# INERTIAL.net
KiCad netlist of a schematic drawn in Altium Designer
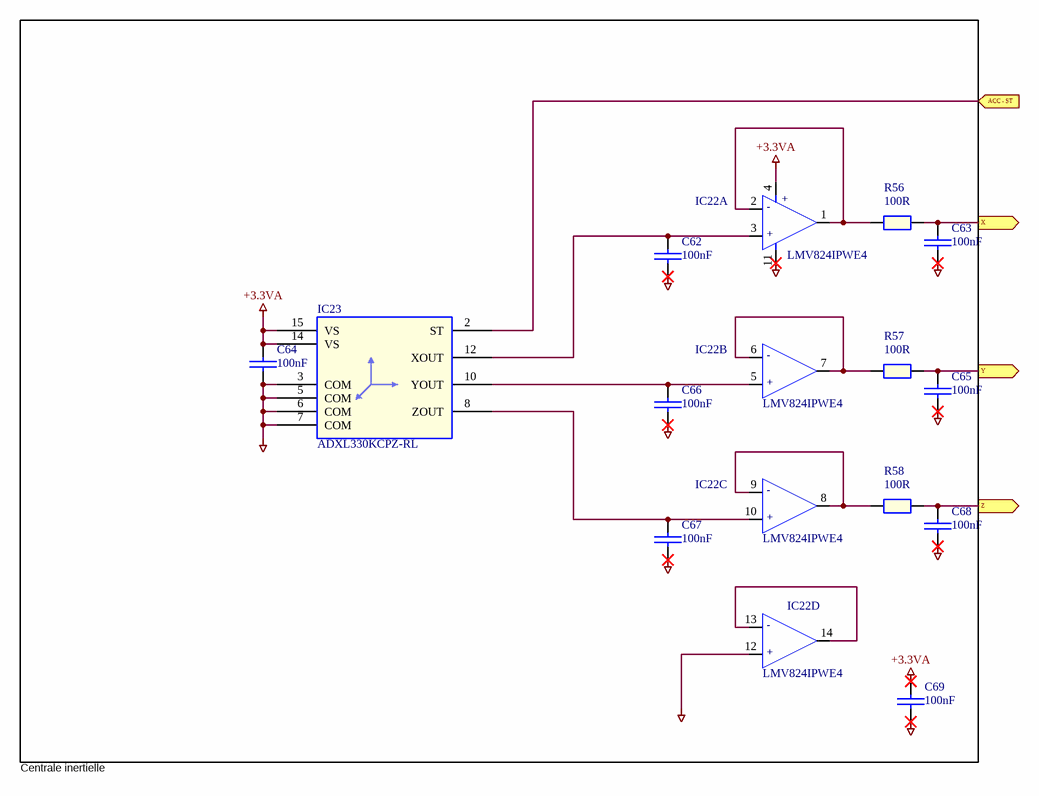
[diagram p0: INERTIAL.SchDoc]

(export (version "E")
  (design (tool "Eeschema 10.0.6"))
  (components
    (comp (ref "C62") (value "100nF") (footprint "SM/C_0805") (libsource (lib "*") (part "C_Dup1")))
    (comp (ref "C63") (value "100nF") (footprint "SM/C_0805") (libsource (lib "*") (part "C_Dup1")))
    (comp (ref "C64") (value "100nF") (footprint "SM/C_0805") (libsource (lib "*") (part "C_Dup1")))
    (comp (ref "C65") (value "100nF") (footprint "SM/C_0805") (libsource (lib "*") (part "C_Dup1")))
    (comp (ref "C66") (value "100nF") (footprint "SM/C_0805") (libsource (lib "*") (part "C_Dup1")))
    (comp (ref "C67") (value "100nF") (footprint "SM/C_0805") (libsource (lib "*") (part "C_Dup1")))
    (comp (ref "C68") (value "100nF") (footprint "SM/C_0805") (libsource (lib "*") (part "C_Dup1")))
    (comp (ref "C69") (value "100nF") (footprint "SM/C_0805") (libsource (lib "*") (part "C_Dup1")))
    (comp (ref "IC22")
      (value "LMV824IPWE4")
      (footprint "HEIG/SM/TSSOP14")
      (libsource (lib "*") (part "AD8609_0"))
    )
    (comp (ref "IC23")
      (value "ADXL330KCPZ-RL")
      (footprint "HEIG/IC/ADXL330")
      (libsource (lib "*") (part "ADXL330"))
    )
    (comp (ref "R56") (value "100R") (footprint "R400") (libsource (lib "*") (part "R_Dup1")))
    (comp (ref "R57") (value "100R") (footprint "R400") (libsource (lib "*") (part "R_Dup1")))
    (comp (ref "R58") (value "100R") (footprint "R400") (libsource (lib "*") (part "R_Dup1")))
  )
  (nets
    (net (code "1") (name "+3.3VA") (class "Default")
      (node (ref "C64") (pin "1") (pinfunction "1_1") (pintype "passive"))
      (node (ref "C69") (pin "1") (pinfunction "1_1") (pintype "passive"))
      (node (ref "IC22") (pin "4") (pinfunction "V+_4") (pintype "passive"))
      (node (ref "IC23") (pin "14") (pinfunction "VS_14") (pintype "passive"))
      (node (ref "IC23") (pin "15") (pinfunction "VS_15") (pintype "passive"))
    )
    (net (code "2") (name "/ACC - ST") (class "Default")
      (node (ref "IC23") (pin "2") (pinfunction "ST_2") (pintype "passive"))
    )
    (net (code "3") (name "/X") (class "Default")
      (node (ref "C63") (pin "1") (pinfunction "1_1") (pintype "passive"))
      (node (ref "R56") (pin "2") (pinfunction "2_2") (pintype "passive"))
    )
    (net (code "4") (name "/Y") (class "Default")
      (node (ref "C65") (pin "1") (pinfunction "1_1") (pintype "passive"))
      (node (ref "R57") (pin "2") (pinfunction "2_2") (pintype "passive"))
    )
    (net (code "5") (name "/Z") (class "Default")
      (node (ref "C68") (pin "1") (pinfunction "1_1") (pintype "passive"))
      (node (ref "R58") (pin "2") (pinfunction "2_2") (pintype "passive"))
    )
    (net (code "6") (name "AGND") (class "Default")
      (node (ref "C62") (pin "2") (pinfunction "2_2") (pintype "passive"))
      (node (ref "C63") (pin "2") (pinfunction "2_2") (pintype "passive"))
      (node (ref "C64") (pin "2") (pinfunction "2_2") (pintype "passive"))
      (node (ref "C65") (pin "2") (pinfunction "2_2") (pintype "passive"))
      (node (ref "C66") (pin "2") (pinfunction "2_2") (pintype "passive"))
      (node (ref "C67") (pin "2") (pinfunction "2_2") (pintype "passive"))
      (node (ref "C68") (pin "2") (pinfunction "2_2") (pintype "passive"))
      (node (ref "C69") (pin "2") (pinfunction "2_2") (pintype "passive"))
      (node (ref "IC22") (pin "11") (pinfunction "V-_11") (pintype "passive"))
      (node (ref "IC22") (pin "12") (pinfunction "+IN_D_12") (pintype "passive"))
      (node (ref "IC23") (pin "3") (pinfunction "COM_3") (pintype "passive"))
      (node (ref "IC23") (pin "5") (pinfunction "COM_5") (pintype "passive"))
      (node (ref "IC23") (pin "6") (pinfunction "COM_6") (pintype "passive"))
      (node (ref "IC23") (pin "7") (pinfunction "COM_7") (pintype "passive"))
    )
    (net (code "7") (name "Net-(IC22A-+IN_A)") (class "Default")
      (node (ref "C62") (pin "1") (pinfunction "1_1") (pintype "passive"))
      (node (ref "IC22") (pin "3") (pinfunction "+IN_A_3") (pintype "passive"))
      (node (ref "IC23") (pin "12") (pinfunction "XOUT_12") (pintype "passive"))
    )
    (net (code "8") (name "Net-(IC22A--IN_A)") (class "Default")
      (node (ref "IC22") (pin "1") (pinfunction "OUT_A_1") (pintype "passive"))
      (node (ref "IC22") (pin "2") (pinfunction "-IN_A_2") (pintype "passive"))
      (node (ref "R56") (pin "1") (pinfunction "1_1") (pintype "passive"))
    )
    (net (code "9") (name "Net-(IC22B-+IN_B)") (class "Default")
      (node (ref "C66") (pin "1") (pinfunction "1_1") (pintype "passive"))
      (node (ref "IC22") (pin "5") (pinfunction "+IN_B_5") (pintype "passive"))
      (node (ref "IC23") (pin "10") (pinfunction "YOUT_10") (pintype "passive"))
    )
    (net (code "10") (name "Net-(IC22B--IN_B)") (class "Default")
      (node (ref "IC22") (pin "6") (pinfunction "-IN_B_6") (pintype "passive"))
      (node (ref "IC22") (pin "7") (pinfunction "OUT_B_7") (pintype "passive"))
      (node (ref "R57") (pin "1") (pinfunction "1_1") (pintype "passive"))
    )
    (net (code "11") (name "Net-(IC22C-+IN_C)") (class "Default")
      (node (ref "C67") (pin "1") (pinfunction "1_1") (pintype "passive"))
      (node (ref "IC22") (pin "10") (pinfunction "+IN_C_10") (pintype "passive"))
      (node (ref "IC23") (pin "8") (pinfunction "ZOUT_8") (pintype "passive"))
    )
    (net (code "12") (name "Net-(IC22C--IN_C)") (class "Default")
      (node (ref "IC22") (pin "8") (pinfunction "OUT_C_8") (pintype "passive"))
      (node (ref "IC22") (pin "9") (pinfunction "-IN_C_9") (pintype "passive"))
      (node (ref "R58") (pin "1") (pinfunction "1_1") (pintype "passive"))
    )
    (net (code "13") (name "Net-(IC22D--IN_D)") (class "Default")
      (node (ref "IC22") (pin "13") (pinfunction "-IN_D_13") (pintype "passive"))
      (node (ref "IC22") (pin "14") (pinfunction "OUT_D_14") (pintype "passive"))
    )
  )
)
